# IR.net
KiCad netlist of a schematic drawn in Altium Designer
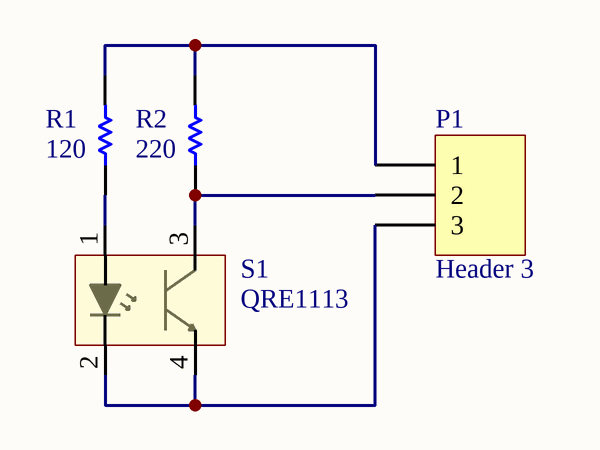
[diagram p0: IR.SchDoc]

(export (version "E")
  (design (tool "Eeschema 10.0.6"))
  (components
    (comp (ref "P1")
      (value "Header 3")
      (footprint "HDR1X3")
      (description "Header, 3-Pin")
      (fields (field (name "PUBLISHER") "Altium Limited"))
      (libsource (lib "Miscellaneous Connectors") (part "Header 3"))
    )
    (comp (ref "R1")
      (value "120")
      (footprint "J1-0603")
      (description "Resistor")
      (fields (field (name "Comment") "Res1") (field (name "PUBLISHER") "Altium Limited"))
      (libsource (lib "Miscellaneous Devices") (part "Res1"))
    )
    (comp (ref "R2")
      (value "220")
      (footprint "J1-0603")
      (description "Resistor")
      (fields (field (name "Comment") "Res1") (field (name "PUBLISHER") "Altium Limited"))
      (libsource (lib "Miscellaneous Devices") (part "Res1"))
    )
    (comp (ref "S1") (value "QRE1113") (footprint "QRE1113GR") (libsource (lib "IR") (part "QRE1113")))
  )
  (nets
    (net (code "1") (name "Net-(P1-Pad1)") (class "Default")
      (node (ref "P1") (pin "1") (pinfunction "1_1") (pintype "passive"))
      (node (ref "R1") (pin "2") (pinfunction "2_2") (pintype "passive"))
      (node (ref "R2") (pin "2") (pinfunction "2_2") (pintype "passive"))
    )
    (net (code "2") (name "Net-(P1-Pad2)") (class "Default")
      (node (ref "P1") (pin "2") (pinfunction "2_2") (pintype "passive"))
      (node (ref "R2") (pin "1") (pinfunction "1_1") (pintype "passive"))
      (node (ref "S1") (pin "3") (pinfunction "+_3") (pintype "passive"))
    )
    (net (code "3") (name "Net-(R1-Pad1)") (class "Default")
      (node (ref "R1") (pin "1") (pinfunction "1_1") (pintype "passive"))
      (node (ref "S1") (pin "1") (pinfunction "+_1") (pintype "passive"))
    )
    (net (code "4") (name "Net-(S1-5)") (class "Default")
      (node (ref "P1") (pin "3") (pinfunction "3_3") (pintype "passive"))
      (node (ref "S1") (pin "2") (pinfunction "5_2") (pintype "passive"))
      (node (ref "S1") (pin "4") (pinfunction "4_4") (pintype "passive"))
    )
  )
)
